# IoT_Shield_V1.net
KiCad netlist of a schematic drawn in EAGLE
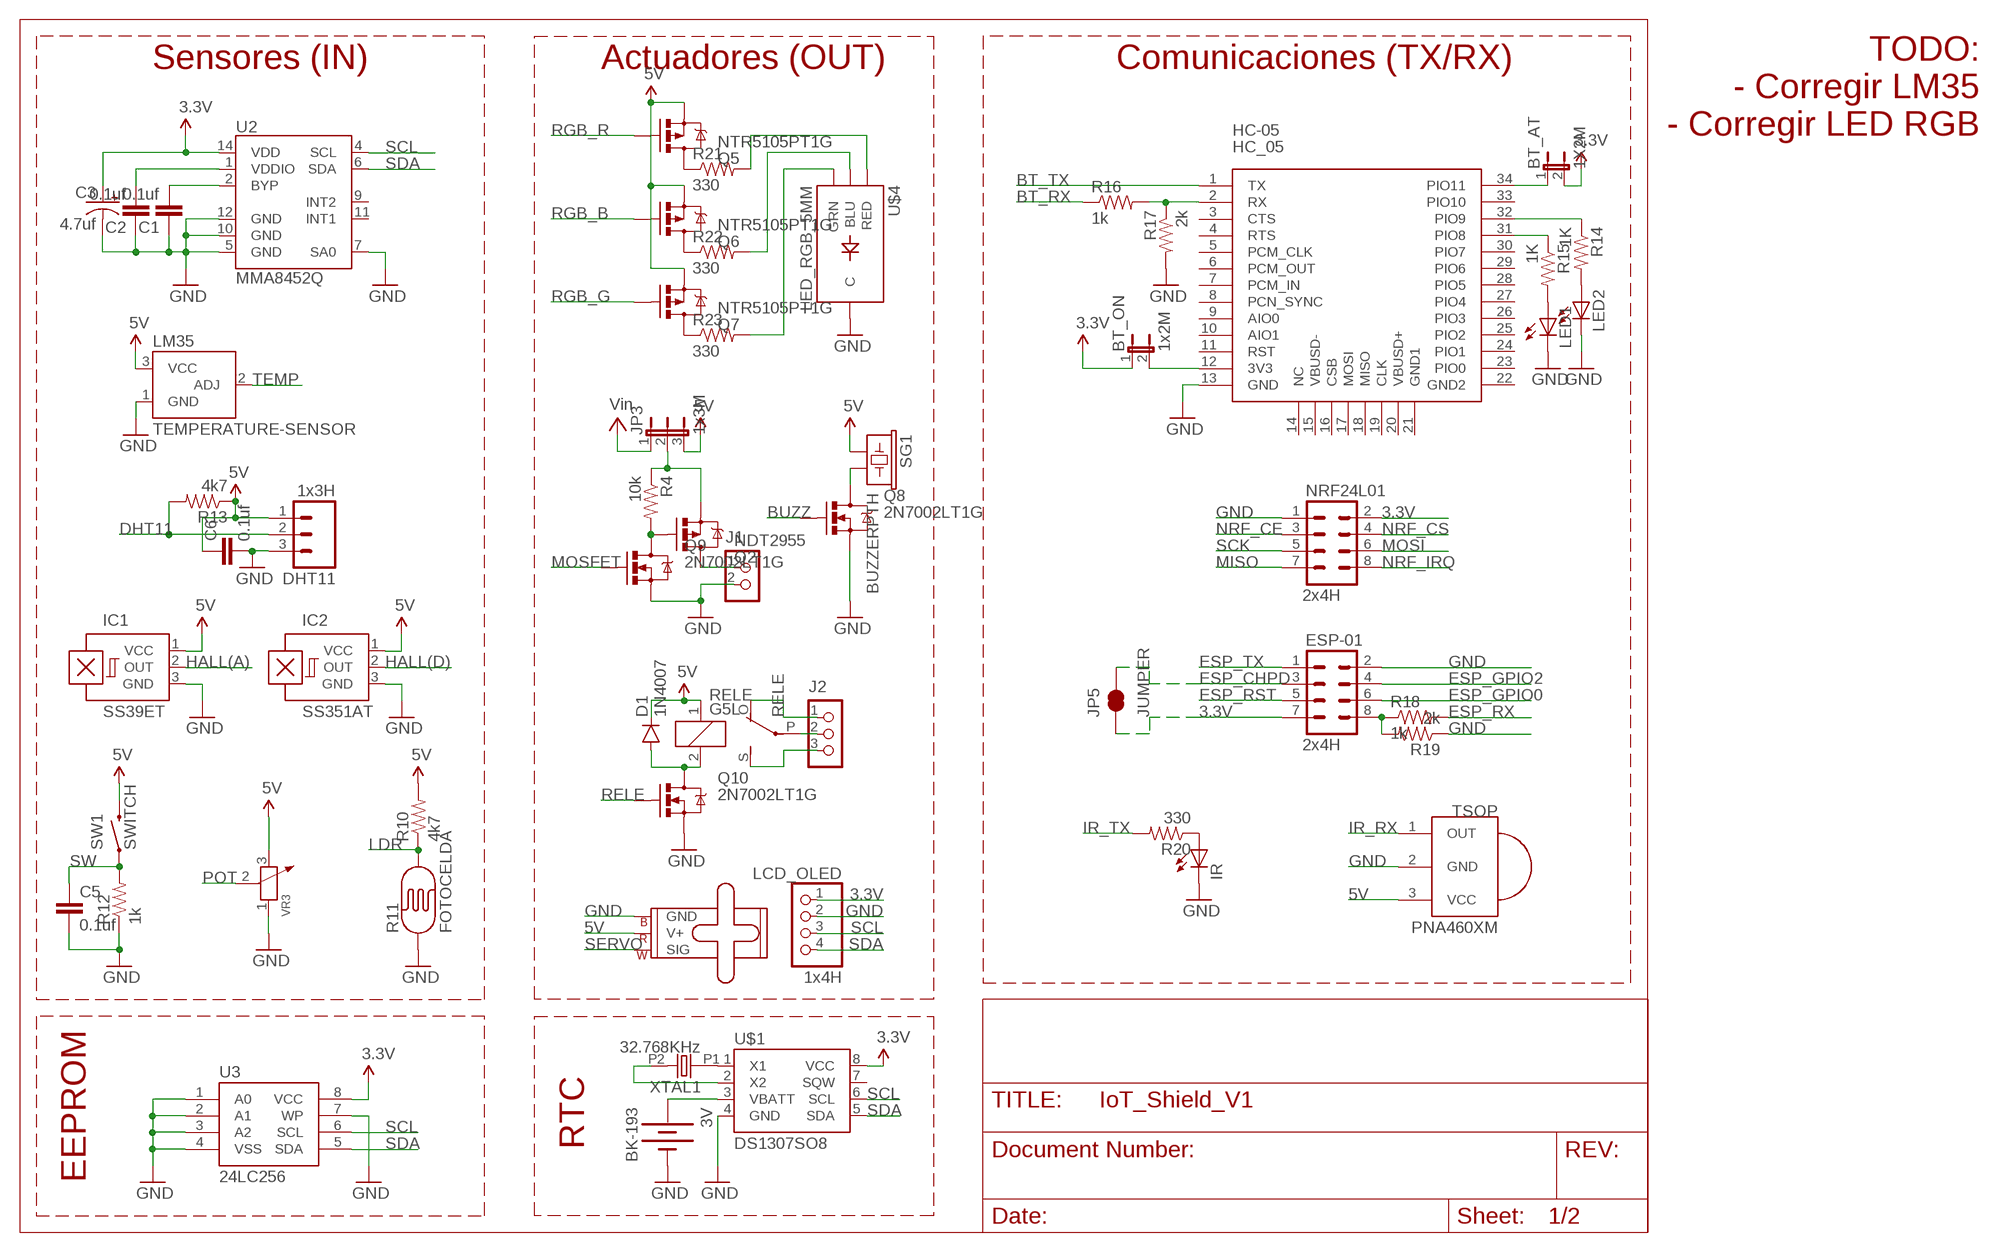
[diagram p0: schematic, sheet 1]
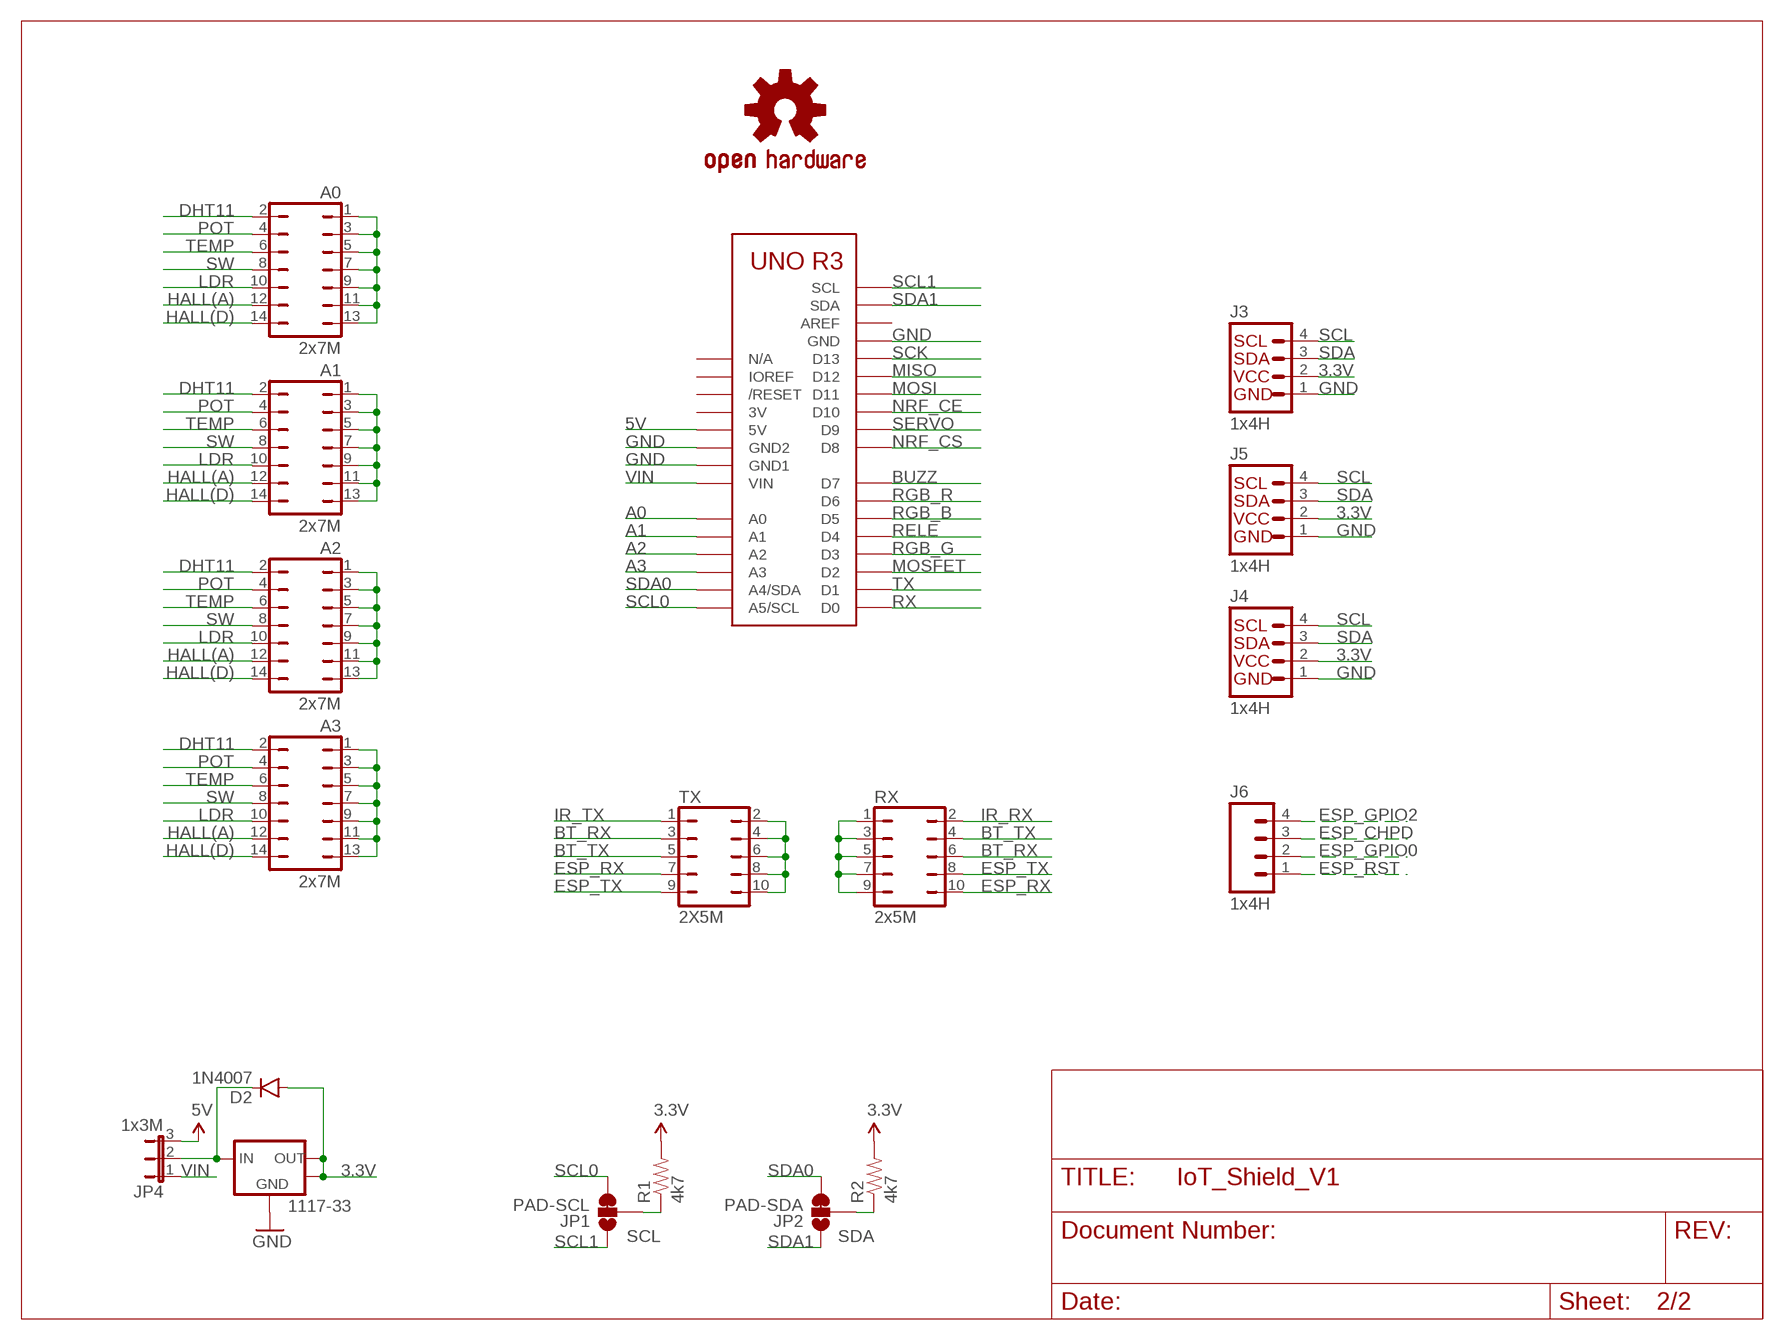
[diagram p1: schematic, sheet 2]

(export (version "E")
  (design (tool "Eeschema 10.0.6"))
  (components
    (comp (ref "3V")
      (value "BK-193")
      (footprint "eagle-import:BATTERY-20MMTH")
      (libsource (lib "eagle-import") (part "BK-193"))
    )
    (comp (ref "BT_AT")
      (value "1X2M")
      (footprint "eagle-import:JP1")
      (libsource (lib "eagle-import") (part "JP1E"))
    )
    (comp (ref "BT_ON")
      (value "1x2M")
      (footprint "eagle-import:JP1")
      (libsource (lib "eagle-import") (part "JP1E"))
    )
    (comp (ref "C1")
      (value "0.1uf")
      (footprint "eagle-import:0805")
      (libsource (lib "eagle-import") (part "CAP0805"))
    )
    (comp (ref "C2")
      (value "0.1uf")
      (footprint "eagle-import:0805")
      (libsource (lib "eagle-import") (part "CAP0805"))
    )
    (comp (ref "C3")
      (value "4.7uf")
      (footprint "eagle-import:EIA3528-KIT")
      (libsource (lib "eagle-import") (part "CAP_POL3528-KIT"))
    )
    (comp (ref "C5")
      (value "0.1uf")
      (footprint "eagle-import:0805")
      (libsource (lib "eagle-import") (part "SparkFun-Passives_CAP0805"))
    )
    (comp (ref "C6")
      (value "0.1uf")
      (footprint "eagle-import:0805")
      (libsource (lib "eagle-import") (part "SparkFun-Passives_CAP0805"))
    )
    (comp (ref "D1")
      (value "1N4007")
      (footprint "eagle-import:SMA-DIODE")
      (libsource (lib "eagle-import") (part "DIODESMA"))
    )
    (comp (ref "DHT11")
      (value "1x3H")
      (footprint "eagle-import:1X03_LOCK")
      (libsource (lib "eagle-import") (part "M03LOCK"))
    )
    (comp (ref "ESP-01")
      (value "2x4H")
      (footprint "eagle-import:2X4")
      (libsource (lib "eagle-import") (part "M04X2"))
    )
    (comp (ref "HC-05")
      (value "HC_05")
      (footprint "eagle-import:BLUETOOTH_SMD")
      (libsource (lib "eagle-import") (part "HC_05"))
    )
    (comp (ref "IC1")
      (value "SS39ET")
      (footprint "eagle-import:SOT23-W")
      (libsource (lib "eagle-import") (part "A12?LH02"))
    )
    (comp (ref "IC2")
      (value "SS351AT")
      (footprint "eagle-import:SOT23-W")
      (libsource (lib "eagle-import") (part "A12?LH02"))
    )
    (comp (ref "IR")
      (value "LEDIRL80A")
      (footprint "eagle-import:IRL80A")
      (libsource (lib "eagle-import") (part "led_LEDIRL80A"))
    )
    (comp (ref "J1")
      (value "CON_TERMINAL_BLOCK_02-5MM")
      (footprint "eagle-import:TERMINAL_BLOCK_2P_5")
      (libsource (lib "eagle-import") (part "CON_TERMINAL_BLOCK_02-5MM"))
    )
    (comp (ref "J2")
      (value "CON_TERMINAL_BLOCK_03-5MM")
      (footprint "eagle-import:TERMINAL_BLOCK_3P_5")
      (libsource (lib "eagle-import") (part "CON_TERMINAL_BLOCK_03-5MM"))
    )
    (comp (ref "JP3")
      (value "1x3M")
      (footprint "eagle-import:JP2")
      (libsource (lib "eagle-import") (part "JP2E"))
    )
    (comp (ref "JP5")
      (value "JUMPER")
      (footprint "eagle-import:PAD-JUMPER-2-NC_BY_TRACE_NO_SILK")
      (libsource (lib "eagle-import") (part "JUMPER-PAD-2-NC_BY_TRACENO_SILK"))
    )
    (comp (ref "LCD_OLED")
      (value "1x4H")
      (footprint "eagle-import:1X04")
      (libsource (lib "eagle-import") (part "PINHD-1X4"))
    )
    (comp (ref "LED1")
      (value "LEDCHIPLED_0805")
      (footprint "eagle-import:CHIPLED_0805")
      (libsource (lib "eagle-import") (part "LEDCHIPLED_0805"))
    )
    (comp (ref "LED2")
      (value "LEDCHIPLED_0805")
      (footprint "eagle-import:CHIPLED_0805")
      (libsource (lib "eagle-import") (part "LEDCHIPLED_0805"))
    )
    (comp (ref "LM35")
      (value "TEMPERATURE-SENSOR")
      (footprint "eagle-import:TO-92")
      (libsource (lib "eagle-import") (part "TEMPERATURE-SENSOR"))
    )
    (comp (ref "NRF24L01")
      (value "2x4H")
      (footprint "eagle-import:2X4")
      (libsource (lib "eagle-import") (part "M04X2"))
    )
    (comp (ref "Q2")
      (value "NDT2955")
      (footprint "eagle-import:SOT223")
      (libsource (lib "eagle-import") (part "NDT2955"))
    )
    (comp (ref "Q5")
      (value "NTR5105PT1G")
      (footprint "eagle-import:SOT23-3")
      (libsource (lib "eagle-import") (part "MOSFET-PCHANNEL"))
    )
    (comp (ref "Q6")
      (value "NTR5105PT1G")
      (footprint "eagle-import:SOT23-3")
      (libsource (lib "eagle-import") (part "MOSFET-PCHANNEL"))
    )
    (comp (ref "Q7")
      (value "NTR5105PT1G")
      (footprint "eagle-import:SOT23-3")
      (libsource (lib "eagle-import") (part "MOSFET-PCHANNEL"))
    )
    (comp (ref "Q8")
      (value "2N7002LT1G")
      (footprint "eagle-import:SOT23-3")
      (libsource (lib "eagle-import") (part "MOSFET-NCHANNELAO3404A"))
    )
    (comp (ref "Q9")
      (value "2N7002LT1G")
      (footprint "eagle-import:SOT23-3")
      (libsource (lib "eagle-import") (part "MOSFET-NCHANNELAO3404A"))
    )
    (comp (ref "Q10")
      (value "2N7002LT1G")
      (footprint "eagle-import:SOT23-3")
      (libsource (lib "eagle-import") (part "MOSFET-NCHANNELAO3404A"))
    )
    (comp (ref "R4")
      (value "10k")
      (footprint "eagle-import:0805")
      (libsource (lib "eagle-import") (part "RESISTOR0805-RES"))
    )
    (comp (ref "R10")
      (value "4k7")
      (footprint "eagle-import:0805")
      (libsource (lib "eagle-import") (part "RESISTOR0805-RES"))
    )
    (comp (ref "R11")
      (value "FOTOCELDA")
      (footprint "eagle-import:PHOTOCELL")
      (libsource (lib "eagle-import") (part "PHOTOCELLPTH"))
    )
    (comp (ref "R12")
      (value "1k")
      (footprint "eagle-import:0805")
      (libsource (lib "eagle-import") (part "RESISTOR0805-RES"))
    )
    (comp (ref "R13")
      (value "4k7")
      (footprint "eagle-import:0805")
      (libsource (lib "eagle-import") (part "RESISTOR0805-RES"))
    )
    (comp (ref "R14")
      (value "1K")
      (footprint "eagle-import:0805")
      (libsource (lib "eagle-import") (part "SparkFun-Resistors_RESISTOR0805-RES"))
    )
    (comp (ref "R15")
      (value "1K")
      (footprint "eagle-import:0805")
      (libsource (lib "eagle-import") (part "SparkFun-Resistors_RESISTOR0805-RES"))
    )
    (comp (ref "R16")
      (value "1k")
      (footprint "eagle-import:0805")
      (libsource (lib "eagle-import") (part "SparkFun-Resistors_RESISTOR0805-RES"))
    )
    (comp (ref "R17")
      (value "2k")
      (footprint "eagle-import:0805")
      (libsource (lib "eagle-import") (part "SparkFun-Resistors_RESISTOR0805-RES"))
    )
    (comp (ref "R18")
      (value "1k")
      (footprint "eagle-import:0805")
      (libsource (lib "eagle-import") (part "SparkFun-Resistors_RESISTOR0805-RES"))
    )
    (comp (ref "R19")
      (value "2k")
      (footprint "eagle-import:0805")
      (libsource (lib "eagle-import") (part "SparkFun-Resistors_RESISTOR0805-RES"))
    )
    (comp (ref "R20")
      (value "330")
      (footprint "eagle-import:1206")
      (libsource (lib "eagle-import") (part "RESISTOR1206"))
    )
    (comp (ref "R21")
      (value "330")
      (footprint "eagle-import:1206")
      (libsource (lib "eagle-import") (part "RESISTOR1206"))
    )
    (comp (ref "R22")
      (value "330")
      (footprint "eagle-import:1206")
      (libsource (lib "eagle-import") (part "RESISTOR1206"))
    )
    (comp (ref "R23")
      (value "330")
      (footprint "eagle-import:1206")
      (libsource (lib "eagle-import") (part "RESISTOR1206"))
    )
    (comp (ref "RELE")
      (value "G5L")
      (footprint "eagle-import:G5LE")
      (libsource (lib "eagle-import") (part "G5L"))
    )
    (comp (ref "SERVO")
      (value "1X3M")
      (footprint "eagle-import:1X03")
      (libsource (lib "eagle-import") (part "SMALL_SERVO"))
    )
    (comp (ref "SG1")
      (value "BUZZERPTH")
      (footprint "eagle-import:BUZZER-12MM")
      (libsource (lib "eagle-import") (part "BUZZERPTH"))
    )
    (comp (ref "SW1")
      (value "SWITCH")
      (footprint "eagle-import:TACTILE-PTH")
      (libsource (lib "eagle-import") (part "SWITCH-MOMENTARY-2PTH"))
    )
    (comp (ref "TSOP")
      (value "PNA460XM")
      (footprint "eagle-import:PNA460XM")
      (libsource (lib "eagle-import") (part "PNA460XM"))
    )
    (comp (ref "U$1")
      (value "DS1307SO8")
      (footprint "eagle-import:SO08")
      (libsource (lib "eagle-import") (part "DS1307SO8"))
    )
    (comp (ref "U$4")
      (value "LED_RGB_5MM")
      (footprint "eagle-import:LED_PIRANHA_5MM")
      (libsource (lib "eagle-import") (part "LED_PIRANHA_5MM"))
    )
    (comp (ref "U2")
      (value "MMA8452Q")
      (footprint "eagle-import:QFN-16_0.5MM")
      (libsource (lib "eagle-import") (part "MMA8452Q"))
    )
    (comp (ref "U3")
      (value "24LC256")
      (footprint "eagle-import:SO08")
      (libsource (lib "eagle-import") (part "EEPROM-I2CSMD"))
    )
    (comp (ref "VR3")
      (value "RES-ADJ'WH121-1'")
      (footprint "eagle-import:ADJR2+3P-16.0X12.0X18.0MM")
      (libsource (lib "eagle-import") (part "RES-ADJ'WH121-1'"))
    )
    (comp (ref "XTAL1")
      (value "32.768KHz")
      (footprint "eagle-import:TC-26")
      (libsource (lib "eagle-import") (part "OSC-XTALTC-26"))
    )
    (comp (ref "1117-33")
      (value "LV1117-33TO252")
      (footprint "eagle-import:TO252")
      (libsource (lib "eagle-import") (part "LV1117-33TO252"))
    )
    (comp (ref "A0")
      (value "2x7M")
      (footprint "eagle-import:JP7Q")
      (libsource (lib "eagle-import") (part "JP7Q"))
    )
    (comp (ref "A1")
      (value "2x7M")
      (footprint "eagle-import:JP7Q")
      (libsource (lib "eagle-import") (part "JP7Q"))
    )
    (comp (ref "A2")
      (value "2x7M")
      (footprint "eagle-import:JP7Q")
      (libsource (lib "eagle-import") (part "JP7Q"))
    )
    (comp (ref "A3")
      (value "2x7M")
      (footprint "eagle-import:JP7Q")
      (libsource (lib "eagle-import") (part "JP7Q"))
    )
    (comp (ref "D2")
      (value "1N4007")
      (footprint "eagle-import:SMA-DIODE")
      (libsource (lib "eagle-import") (part "DIODESMA"))
    )
    (comp (ref "J3")
      (value "1x4H")
      (footprint "eagle-import:1X04")
      (libsource (lib "eagle-import") (part "I2C_STANDARD"))
    )
    (comp (ref "J4")
      (value "1x4H")
      (footprint "eagle-import:1X04")
      (libsource (lib "eagle-import") (part "I2C_STANDARD"))
    )
    (comp (ref "J5")
      (value "1x4H")
      (footprint "eagle-import:1X04")
      (libsource (lib "eagle-import") (part "I2C_STANDARD"))
    )
    (comp (ref "J6")
      (value "1x4H")
      (footprint "eagle-import:1X04_LOCK")
      (libsource (lib "eagle-import") (part "M04LOCK"))
    )
    (comp (ref "JP1")
      (value "PAD-SCL")
      (footprint "eagle-import:PAD-JUMPER-3-2OF3_NC_BY_TRACE_YES_SILK_LARGE")
      (libsource (lib "eagle-import") (part "JUMPER-PAD-3-2OF3_NC_BY_TRACE_LARGE"))
    )
    (comp (ref "JP2")
      (value "PAD-SDA")
      (footprint "eagle-import:PAD-JUMPER-3-2OF3_NC_BY_TRACE_YES_SILK_LARGE")
      (libsource (lib "eagle-import") (part "JUMPER-PAD-3-2OF3_NC_BY_TRACE_LARGE"))
    )
    (comp (ref "JP4")
      (value "1x3M")
      (footprint "eagle-import:JP2")
      (libsource (lib "eagle-import") (part "JP2E"))
    )
    (comp (ref "LOGO1")
      (value "OSHW-LOGOL-COPPER")
      (footprint "eagle-import:OSHW-LOGO-L_COPPER")
      (libsource (lib "eagle-import") (part "OSHW-LOGOL-COPPER"))
    )
    (comp (ref "R1")
      (value "4k7")
      (footprint "eagle-import:0805")
      (libsource (lib "eagle-import") (part "RESISTOR0805-RES"))
    )
    (comp (ref "R2")
      (value "4k7")
      (footprint "eagle-import:0805")
      (libsource (lib "eagle-import") (part "RESISTOR0805-RES"))
    )
    (comp (ref "RX")
      (value "2x5M")
      (footprint "eagle-import:JP5Q")
      (libsource (lib "eagle-import") (part "JP5Q"))
    )
    (comp (ref "TX")
      (value "2X5M")
      (footprint "eagle-import:JP5Q")
      (libsource (lib "eagle-import") (part "JP5Q"))
    )
    (comp (ref "U1")
      (value "ARDUINOR3-DIMENSION")
      (footprint "eagle-import:ARDUINOR3")
      (libsource (lib "eagle-import") (part "ARDUINOR3-DIMENSION"))
    )
  )
  (nets
    (net (code "1") (name "3.3V") (class "Default")
      (node (ref "1117-33") (pin "2") (pinfunction "OUT_2") (pintype "output"))
      (node (ref "1117-33") (pin "4") (pinfunction "OUT_4") (pintype "output"))
      (node (ref "BT_AT") (pin "2") (pinfunction "2_2") (pintype "passive"))
      (node (ref "BT_ON") (pin "1") (pinfunction "1_1") (pintype "passive"))
      (node (ref "C3") (pin "A") (pinfunction "+_A") (pintype "passive"))
      (node (ref "D2") (pin "A") (pinfunction "A_A") (pintype "passive"))
      (node (ref "ESP-01") (pin "7") (pinfunction "7_7") (pintype "passive"))
      (node (ref "J3") (pin "2") (pinfunction "2_2") (pintype "passive"))
      (node (ref "J4") (pin "2") (pinfunction "2_2") (pintype "passive"))
      (node (ref "J5") (pin "2") (pinfunction "2_2") (pintype "passive"))
      (node (ref "JP5") (pin "1") (pinfunction "1_1") (pintype "passive"))
      (node (ref "LCD_OLED") (pin "1") (pinfunction "1_1") (pintype "passive"))
      (node (ref "NRF24L01") (pin "2") (pinfunction "2_2") (pintype "passive"))
      (node (ref "R1") (pin "2") (pinfunction "2_2") (pintype "passive"))
      (node (ref "R2") (pin "2") (pinfunction "2_2") (pintype "passive"))
      (node (ref "U$1") (pin "8") (pinfunction "VCC_8") (pintype "bidirectional"))
      (node (ref "U2") (pin "14") (pinfunction "VDD_14") (pintype "bidirectional"))
      (node (ref "U3") (pin "8") (pinfunction "VCC_8") (pintype "power_in"))
    )
    (net (code "2") (name "3V") (class "Default")
      (node (ref "U1") (pin "3V") (pinfunction "3V_3V") (pintype "power_in"))
    )
    (net (code "3") (name "5V") (class "Default")
      (node (ref "C6") (pin "1") (pinfunction "1_1") (pintype "passive"))
      (node (ref "D1") (pin "C") (pinfunction "C_C") (pintype "passive"))
      (node (ref "DHT11") (pin "1") (pinfunction "1_1") (pintype "passive"))
      (node (ref "IC1") (pin "1") (pinfunction "VCC_1") (pintype "power_in"))
      (node (ref "IC2") (pin "1") (pinfunction "VCC_1") (pintype "power_in"))
      (node (ref "JP3") (pin "3") (pinfunction "3_3") (pintype "passive"))
      (node (ref "JP4") (pin "3") (pinfunction "3_3") (pintype "passive"))
      (node (ref "LM35") (pin "3") (pinfunction "VCC_3") (pintype "bidirectional"))
      (node (ref "Q5") (pin "2") (pinfunction "S_2") (pintype "passive"))
      (node (ref "Q6") (pin "2") (pinfunction "S_2") (pintype "passive"))
      (node (ref "Q7") (pin "2") (pinfunction "S_2") (pintype "passive"))
      (node (ref "R10") (pin "2") (pinfunction "2_2") (pintype "passive"))
      (node (ref "R13") (pin "1") (pinfunction "1_1") (pintype "passive"))
      (node (ref "RELE") (pin "1") (pinfunction "1_1") (pintype "passive"))
      (node (ref "SERVO") (pin "2") (pinfunction "V+_2") (pintype "bidirectional"))
      (node (ref "SG1") (pin "+") (pinfunction "1_+") (pintype "passive"))
      (node (ref "SW1") (pin "3") (pinfunction "2_3") (pintype "passive"))
      (node (ref "TSOP") (pin "3") (pinfunction "VCC_3") (pintype "power_in"))
      (node (ref "U1") (pin "5V") (pinfunction "5V_5V") (pintype "power_in"))
      (node (ref "VR3") (pin "3") (pinfunction "3_3") (pintype "passive"))
    )
    (net (code "4") (name "A0") (class "Default")
      (node (ref "A0") (pin "1") (pinfunction "1_1") (pintype "passive"))
      (node (ref "A0") (pin "11") (pinfunction "11_11") (pintype "passive"))
      (node (ref "A0") (pin "13") (pinfunction "13_13") (pintype "passive"))
      (node (ref "A0") (pin "3") (pinfunction "3_3") (pintype "passive"))
      (node (ref "A0") (pin "5") (pinfunction "5_5") (pintype "passive"))
      (node (ref "A0") (pin "7") (pinfunction "7_7") (pintype "passive"))
      (node (ref "A0") (pin "9") (pinfunction "9_9") (pintype "passive"))
      (node (ref "U1") (pin "A0") (pinfunction "A0_A0") (pintype "bidirectional"))
    )
    (net (code "5") (name "A1") (class "Default")
      (node (ref "A1") (pin "1") (pinfunction "1_1") (pintype "passive"))
      (node (ref "A1") (pin "11") (pinfunction "11_11") (pintype "passive"))
      (node (ref "A1") (pin "13") (pinfunction "13_13") (pintype "passive"))
      (node (ref "A1") (pin "3") (pinfunction "3_3") (pintype "passive"))
      (node (ref "A1") (pin "5") (pinfunction "5_5") (pintype "passive"))
      (node (ref "A1") (pin "7") (pinfunction "7_7") (pintype "passive"))
      (node (ref "A1") (pin "9") (pinfunction "9_9") (pintype "passive"))
      (node (ref "U1") (pin "A1") (pinfunction "A1_A1") (pintype "bidirectional"))
    )
    (net (code "6") (name "A2") (class "Default")
      (node (ref "A2") (pin "1") (pinfunction "1_1") (pintype "passive"))
      (node (ref "A2") (pin "11") (pinfunction "11_11") (pintype "passive"))
      (node (ref "A2") (pin "13") (pinfunction "13_13") (pintype "passive"))
      (node (ref "A2") (pin "3") (pinfunction "3_3") (pintype "passive"))
      (node (ref "A2") (pin "5") (pinfunction "5_5") (pintype "passive"))
      (node (ref "A2") (pin "7") (pinfunction "7_7") (pintype "passive"))
      (node (ref "A2") (pin "9") (pinfunction "9_9") (pintype "passive"))
      (node (ref "U1") (pin "A2") (pinfunction "A2_A2") (pintype "bidirectional"))
    )
    (net (code "7") (name "A3") (class "Default")
      (node (ref "A3") (pin "1") (pinfunction "1_1") (pintype "passive"))
      (node (ref "A3") (pin "11") (pinfunction "11_11") (pintype "passive"))
      (node (ref "A3") (pin "13") (pinfunction "13_13") (pintype "passive"))
      (node (ref "A3") (pin "3") (pinfunction "3_3") (pintype "passive"))
      (node (ref "A3") (pin "5") (pinfunction "5_5") (pintype "passive"))
      (node (ref "A3") (pin "7") (pinfunction "7_7") (pintype "passive"))
      (node (ref "A3") (pin "9") (pinfunction "9_9") (pintype "passive"))
      (node (ref "U1") (pin "A3") (pinfunction "A3_A3") (pintype "bidirectional"))
    )
    (net (code "8") (name "BT_RX") (class "Default")
      (node (ref "R16") (pin "1") (pinfunction "1_1") (pintype "passive"))
      (node (ref "RX") (pin "6") (pinfunction "6_6") (pintype "passive"))
      (node (ref "TX") (pin "3") (pinfunction "3_3") (pintype "passive"))
    )
    (net (code "9") (name "BT_TX") (class "Default")
      (node (ref "HC-05") (pin "1") (pinfunction "TX_1") (pintype "bidirectional"))
      (node (ref "RX") (pin "4") (pinfunction "4_4") (pintype "passive"))
      (node (ref "TX") (pin "5") (pinfunction "5_5") (pintype "passive"))
    )
    (net (code "10") (name "BUZZ") (class "Default")
      (node (ref "Q8") (pin "1") (pinfunction "G_1") (pintype "passive"))
      (node (ref "U1") (pin "D7") (pinfunction "D7_D7") (pintype "bidirectional"))
    )
    (net (code "11") (name "DHT11") (class "Default")
      (node (ref "A0") (pin "2") (pinfunction "2_2") (pintype "passive"))
      (node (ref "A1") (pin "2") (pinfunction "2_2") (pintype "passive"))
      (node (ref "A2") (pin "2") (pinfunction "2_2") (pintype "passive"))
      (node (ref "A3") (pin "2") (pinfunction "2_2") (pintype "passive"))
      (node (ref "DHT11") (pin "2") (pinfunction "2_2") (pintype "passive"))
      (node (ref "R13") (pin "2") (pinfunction "2_2") (pintype "passive"))
    )
    (net (code "12") (name "ESP_CHPD") (class "Default")
      (node (ref "ESP-01") (pin "3") (pinfunction "3_3") (pintype "passive"))
      (node (ref "J6") (pin "3") (pinfunction "3_3") (pintype "passive"))
      (node (ref "JP5") (pin "2") (pinfunction "2_2") (pintype "passive"))
    )
    (net (code "13") (name "ESP_GPIO0") (class "Default")
      (node (ref "ESP-01") (pin "6") (pinfunction "6_6") (pintype "passive"))
      (node (ref "J6") (pin "2") (pinfunction "2_2") (pintype "passive"))
    )
    (net (code "14") (name "ESP_GPIO2") (class "Default")
      (node (ref "ESP-01") (pin "4") (pinfunction "4_4") (pintype "passive"))
      (node (ref "J6") (pin "4") (pinfunction "4_4") (pintype "passive"))
    )
    (net (code "15") (name "ESP_RST") (class "Default")
      (node (ref "ESP-01") (pin "5") (pinfunction "5_5") (pintype "passive"))
      (node (ref "J6") (pin "1") (pinfunction "1_1") (pintype "passive"))
    )
    (net (code "16") (name "ESP_RX") (class "Default")
      (node (ref "R18") (pin "2") (pinfunction "2_2") (pintype "passive"))
      (node (ref "RX") (pin "10") (pinfunction "10_10") (pintype "passive"))
      (node (ref "TX") (pin "7") (pinfunction "7_7") (pintype "passive"))
    )
    (net (code "17") (name "ESP_TX") (class "Default")
      (node (ref "ESP-01") (pin "1") (pinfunction "1_1") (pintype "passive"))
      (node (ref "RX") (pin "8") (pinfunction "8_8") (pintype "passive"))
      (node (ref "TX") (pin "9") (pinfunction "9_9") (pintype "passive"))
    )
    (net (code "18") (name "GND") (class "Default")
      (node (ref "1117-33") (pin "1") (pinfunction "ADJ_1") (pintype "input"))
      (node (ref "3V") (pin "P1-") (pinfunction "-_P1-") (pintype "power_in"))
      (node (ref "C1") (pin "1") (pinfunction "1_1") (pintype "passive"))
      (node (ref "C2") (pin "1") (pinfunction "1_1") (pintype "passive"))
      (node (ref "C3") (pin "C") (pinfunction "-_C") (pintype "passive"))
      (node (ref "C5") (pin "2") (pinfunction "2_2") (pintype "passive"))
      (node (ref "C6") (pin "2") (pinfunction "2_2") (pintype "passive"))
      (node (ref "DHT11") (pin "3") (pinfunction "3_3") (pintype "passive"))
      (node (ref "ESP-01") (pin "2") (pinfunction "2_2") (pintype "passive"))
      (node (ref "HC-05") (pin "13") (pinfunction "GND_13") (pintype "bidirectional"))
      (node (ref "IC1") (pin "3") (pinfunction "GND_3") (pintype "power_in"))
      (node (ref "IC2") (pin "3") (pinfunction "GND_3") (pintype "power_in"))
      (node (ref "IR") (pin "K") (pinfunction "C_K") (pintype "passive"))
      (node (ref "J1") (pin "2") (pinfunction "2_2") (pintype "passive"))
      (node (ref "J3") (pin "1") (pinfunction "1_1") (pintype "passive"))
      (node (ref "J4") (pin "1") (pinfunction "1_1") (pintype "passive"))
      (node (ref "J5") (pin "1") (pinfunction "1_1") (pintype "passive"))
      (node (ref "LCD_OLED") (pin "2") (pinfunction "2_2") (pintype "passive"))
      (node (ref "LED1") (pin "C") (pinfunction "C_C") (pintype "passive"))
      (node (ref "LED2") (pin "C") (pinfunction "C_C") (pintype "passive"))
      (node (ref "LM35") (pin "1") (pinfunction "GND_1") (pintype "bidirectional"))
      (node (ref "NRF24L01") (pin "1") (pinfunction "1_1") (pintype "passive"))
      (node (ref "Q10") (pin "2") (pinfunction "S_2") (pintype "passive"))
      (node (ref "Q8") (pin "2") (pinfunction "S_2") (pintype "passive"))
      (node (ref "Q9") (pin "2") (pinfunction "S_2") (pintype "passive"))
      (node (ref "R11") (pin "1") (pinfunction "P$1_1") (pintype "bidirectional"))
      (node (ref "R12") (pin "1") (pinfunction "1_1") (pintype "passive"))
      (node (ref "R17") (pin "2") (pinfunction "2_2") (pintype "passive"))
      (node (ref "R19") (pin "1") (pinfunction "1_1") (pintype "passive"))
      (node (ref "SERVO") (pin "3") (pinfunction "GND_3") (pintype "bidirectional"))
      (node (ref "TSOP") (pin "2") (pinfunction "GND_2") (pintype "power_in"))
      (node (ref "U$1") (pin "4") (pinfunction "GND_4") (pintype "bidirectional"))
      (node (ref "U$4") (pin "-") (pinfunction "C_-") (pintype "bidirectional"))
      (node (ref "U1") (pin "GND") (pinfunction "GND_GND") (pintype "power_in"))
      (node (ref "U1") (pin "GND1") (pinfunction "GND1_GND1") (pintype "power_in"))
      (node (ref "U1") (pin "GND2") (pinfunction "GND2_GND2") (pintype "power_in"))
      (node (ref "U2") (pin "10") (pinfunction "GND_10") (pintype "bidirectional"))
      (node (ref "U2") (pin "12") (pinfunction "GND_12") (pintype "bidirectional"))
      (node (ref "U2") (pin "5") (pinfunction "GND_5") (pintype "bidirectional"))
      (node (ref "U2") (pin "7") (pinfunction "SA0_7") (pintype "bidirectional"))
      (node (ref "U3") (pin "1") (pinfunction "A0_1") (pintype "bidirectional"))
      (node (ref "U3") (pin "2") (pinfunction "A1_2") (pintype "bidirectional"))
      (node (ref "U3") (pin "3") (pinfunction "A2_3") (pintype "bidirectional"))
      (node (ref "U3") (pin "4") (pinfunction "VSS_4") (pintype "power_in"))
      (node (ref "U3") (pin "7") (pinfunction "WP_7") (pintype "bidirectional"))
      (node (ref "VR3") (pin "1") (pinfunction "1_1") (pintype "passive"))
    )
    (net (code "19") (name "HALL(A)") (class "Default")
      (node (ref "A0") (pin "12") (pinfunction "12_12") (pintype "passive"))
      (node (ref "A1") (pin "12") (pinfunction "12_12") (pintype "passive"))
      (node (ref "A2") (pin "12") (pinfunction "12_12") (pintype "passive"))
      (node (ref "A3") (pin "12") (pinfunction "12_12") (pintype "passive"))
      (node (ref "IC1") (pin "2") (pinfunction "OUT_2") (pintype "output"))
    )
    (net (code "20") (name "HALL(D)") (class "Default")
      (node (ref "A0") (pin "14") (pinfunction "14_14") (pintype "passive"))
      (node (ref "A1") (pin "14") (pinfunction "14_14") (pintype "passive"))
      (node (ref "A2") (pin "14") (pinfunction "14_14") (pintype "passive"))
      (node (ref "A3") (pin "14") (pinfunction "14_14") (pintype "passive"))
      (node (ref "IC2") (pin "2") (pinfunction "OUT_2") (pintype "output"))
    )
    (net (code "21") (name "IR_RX") (class "Default")
      (node (ref "RX") (pin "2") (pinfunction "2_2") (pintype "passive"))
      (node (ref "TSOP") (pin "1") (pinfunction "OUT_1") (pintype "output"))
    )
    (net (code "22") (name "IR_TX") (class "Default")
      (node (ref "R20") (pin "2") (pinfunction "2_2") (pintype "passive"))
      (node (ref "TX") (pin "1") (pinfunction "1_1") (pintype "passive"))
    )
    (net (code "23") (name "LDR") (class "Default")
      (node (ref "A0") (pin "10") (pinfunction "10_10") (pintype "passive"))
      (node (ref "A1") (pin "10") (pinfunction "10_10") (pintype "passive"))
      (node (ref "A2") (pin "10") (pinfunction "10_10") (pintype "passive"))
      (node (ref "A3") (pin "10") (pinfunction "10_10") (pintype "passive"))
      (node (ref "R10") (pin "1") (pinfunction "1_1") (pintype "passive"))
      (node (ref "R11") (pin "2") (pinfunction "P$2_2") (pintype "bidirectional"))
    )
    (net (code "24") (name "MISO") (class "Default")
      (node (ref "NRF24L01") (pin "7") (pinfunction "7_7") (pintype "passive"))
      (node (ref "U1") (pin "D12") (pinfunction "D12_D12") (pintype "bidirectional"))
    )
    (net (code "25") (name "MOSFET") (class "Default")
      (node (ref "Q9") (pin "1") (pinfunction "G_1") (pintype "passive"))
      (node (ref "U1") (pin "D2") (pinfunction "D2_D2") (pintype "bidirectional"))
    )
    (net (code "26") (name "MOSI") (class "Default")
      (node (ref "NRF24L01") (pin "6") (pinfunction "6_6") (pintype "passive"))
      (node (ref "U1") (pin "D11") (pinfunction "D11_D11") (pintype "bidirectional"))
    )
    (net (code "27") (name "NRF_CE") (class "Default")
      (node (ref "NRF24L01") (pin "3") (pinfunction "3_3") (pintype "passive"))
      (node (ref "U1") (pin "D10") (pinfunction "D10_D10") (pintype "bidirectional"))
    )
    (net (code "28") (name "NRF_CS") (class "Default")
      (node (ref "NRF24L01") (pin "4") (pinfunction "4_4") (pintype "passive"))
      (node (ref "U1") (pin "D8") (pinfunction "D8_D8") (pintype "bidirectional"))
    )
    (net (code "29") (name "NRF_IRQ") (class "Default")
      (node (ref "NRF24L01") (pin "8") (pinfunction "8_8") (pintype "passive"))
    )
    (net (code "30") (name "Net-(1117-33-IN)") (class "Default")
      (node (ref "1117-33") (pin "3") (pinfunction "IN_3") (pintype "input"))
      (node (ref "D2") (pin "C") (pinfunction "C_C") (pintype "passive"))
      (node (ref "JP4") (pin "2") (pinfunction "2_2") (pintype "passive"))
    )
    (net (code "31") (name "Net-(ESP-01-Pad8)") (class "Default")
      (node (ref "ESP-01") (pin "8") (pinfunction "8_8") (pintype "passive"))
      (node (ref "R18") (pin "1") (pinfunction "1_1") (pintype "passive"))
      (node (ref "R19") (pin "2") (pinfunction "2_2") (pintype "passive"))
    )
    (net (code "32") (name "Net-(HC-05-3V3)") (class "Default")
      (node (ref "BT_ON") (pin "2") (pinfunction "2_2") (pintype "passive"))
      (node (ref "HC-05") (pin "12") (pinfunction "3V3_12") (pintype "bidirectional"))
    )
    (net (code "33") (name "Net-(HC-05-PIO8)") (class "Default")
      (node (ref "HC-05") (pin "31") (pinfunction "PIO8_31") (pintype "bidirectional"))
      (node (ref "R15") (pin "1") (pinfunction "1_1") (pintype "passive"))
    )
    (net (code "34") (name "Net-(HC-05-PIO9)") (class "Default")
      (node (ref "HC-05") (pin "32") (pinfunction "PIO9_32") (pintype "bidirectional"))
      (node (ref "R14") (pin "1") (pinfunction "1_1") (pintype "passive"))
    )
    (net (code "35") (name "Net-(HC-05-PIO11)") (class "Default")
      (node (ref "BT_AT") (pin "1") (pinfunction "1_1") (pintype "passive"))
      (node (ref "HC-05") (pin "34") (pinfunction "PIO11_34") (pintype "bidirectional"))
    )
    (net (code "36") (name "Net-(HC-05-RX)") (class "Default")
      (node (ref "HC-05") (pin "2") (pinfunction "RX_2") (pintype "bidirectional"))
      (node (ref "R16") (pin "2") (pinfunction "2_2") (pintype "passive"))
      (node (ref "R17") (pin "1") (pinfunction "1_1") (pintype "passive"))
    )
    (net (code "37") (name "Net-(IR-PadA)") (class "Default")
      (node (ref "IR") (pin "A") (pinfunction "A_A") (pintype "passive"))
      (node (ref "R20") (pin "1") (pinfunction "1_1") (pintype "passive"))
    )
    (net (code "38") (name "Net-(J1-Pad1)") (class "Default")
      (node (ref "J1") (pin "1") (pinfunction "1_1") (pintype "passive"))
      (node (ref "Q2") (pin "2") (pinfunction "D_2") (pintype "passive"))
      (node (ref "Q2") (pin "4") (pinfunction "D_4") (pintype "passive"))
    )
    (net (code "39") (name "Net-(J2-Pad1)") (class "Default")
      (node (ref "J2") (pin "1") (pinfunction "1_1") (pintype "bidirectional"))
      (node (ref "RELE") (pin "O") (pinfunction "O_O") (pintype "passive"))
    )
    (net (code "40") (name "Net-(J2-Pad2)") (class "Default")
      (node (ref "J2") (pin "2") (pinfunction "2_2") (pintype "bidirectional"))
      (node (ref "RELE") (pin "P") (pinfunction "P_P") (pintype "passive"))
    )
    (net (code "41") (name "Net-(J2-Pad3)") (class "Default")
      (node (ref "J2") (pin "3") (pinfunction "3_3") (pintype "bidirectional"))
      (node (ref "RELE") (pin "S") (pinfunction "S_S") (pintype "passive"))
    )
    (net (code "42") (name "Net-(LED1-PadA)") (class "Default")
      (node (ref "LED1") (pin "A") (pinfunction "A_A") (pintype "passive"))
      (node (ref "R15") (pin "2") (pinfunction "2_2") (pintype "passive"))
    )
    (net (code "43") (name "Net-(LED2-PadA)") (class "Default")
      (node (ref "LED2") (pin "A") (pinfunction "A_A") (pintype "passive"))
      (node (ref "R14") (pin "2") (pinfunction "2_2") (pintype "passive"))
    )
    (net (code "44") (name "Net-(Q2-G)") (class "Default")
      (node (ref "Q2") (pin "1") (pinfunction "G_1") (pintype "passive"))
      (node (ref "Q9") (pin "3") (pinfunction "D_3") (pintype "passive"))
      (node (ref "R4") (pin "2") (pinfunction "2_2") (pintype "passive"))
    )
    (net (code "45") (name "Net-(Q2-S)") (class "Default")
      (node (ref "JP3") (pin "2") (pinfunction "2_2") (pintype "passive"))
      (node (ref "Q2") (pin "3") (pinfunction "S_3") (pintype "passive"))
      (node (ref "R4") (pin "1") (pinfunction "1_1") (pintype "passive"))
    )
    (net (code "46") (name "Net-(Q5-D)") (class "Default")
      (node (ref "Q5") (pin "3") (pinfunction "D_3") (pintype "passive"))
      (node (ref "R21") (pin "1") (pinfunction "1_1") (pintype "passive"))
    )
    (net (code "47") (name "Net-(Q6-D)") (class "Default")
      (node (ref "Q6") (pin "3") (pinfunction "D_3") (pintype "passive"))
      (node (ref "R22") (pin "1") (pinfunction "1_1") (pintype "passive"))
    )
    (net (code "48") (name "Net-(Q7-D)") (class "Default")
      (node (ref "Q7") (pin "3") (pinfunction "D_3") (pintype "passive"))
      (node (ref "R23") (pin "1") (pinfunction "1_1") (pintype "passive"))
    )
    (net (code "49") (name "Net-(Q8-D)") (class "Default")
      (node (ref "Q8") (pin "3") (pinfunction "D_3") (pintype "passive"))
      (node (ref "SG1") (pin "-") (pinfunction "2_-") (pintype "passive"))
    )
    (net (code "50") (name "Net-(Q10-D)") (class "Default")
      (node (ref "D1") (pin "A") (pinfunction "A_A") (pintype "passive"))
      (node (ref "Q10") (pin "3") (pinfunction "D_3") (pintype "passive"))
      (node (ref "RELE") (pin "2") (pinfunction "2_2") (pintype "passive"))
    )
    (net (code "51") (name "Net-(U$1-VBATT)") (class "Default")
      (node (ref "3V") (pin "P2+") (pinfunction "+_P2+") (pintype "power_in"))
      (node (ref "3V") (pin "P3+") (pinfunction "+_P3+") (pintype "power_in"))
      (node (ref "U$1") (pin "3") (pinfunction "VBATT_3") (pintype "bidirectional"))
    )
    (net (code "52") (name "Net-(U$1-X1)") (class "Default")
      (node (ref "U$1") (pin "1") (pinfunction "X1_1") (pintype "bidirectional"))
      (node (ref "XTAL1") (pin "P1") (pinfunction "1_P1") (pintype "passive"))
    )
    (net (code "53") (name "Net-(U$1-X2)") (class "Default")
      (node (ref "U$1") (pin "2") (pinfunction "X2_2") (pintype "bidirectional"))
      (node (ref "XTAL1") (pin "P2") (pinfunction "2_P2") (pintype "passive"))
    )
    (net (code "54") (name "Net-(U$4-BLU)") (class "Default")
      (node (ref "R22") (pin "2") (pinfunction "2_2") (pintype "passive"))
      (node (ref "U$4") (pin "B") (pinfunction "BLU_B") (pintype "bidirectional"))
    )
    (net (code "55") (name "Net-(U$4-GRN)") (class "Default")
      (node (ref "R23") (pin "2") (pinfunction "2_2") (pintype "passive"))
      (node (ref "U$4") (pin "G") (pinfunction "GRN_G") (pintype "bidirectional"))
    )
    (net (code "56") (name "Net-(U$4-RED)") (class "Default")
      (node (ref "R21") (pin "2") (pinfunction "2_2") (pintype "passive"))
      (node (ref "U$4") (pin "R") (pinfunction "RED_R") (pintype "bidirectional"))
    )
    (net (code "57") (name "Net-(U2-BYP)") (class "Default")
      (node (ref "C1") (pin "2") (pinfunction "2_2") (pintype "passive"))
      (node (ref "U2") (pin "2") (pinfunction "BYP_2") (pintype "bidirectional"))
    )
    (net (code "58") (name "Net-(U2-VDDIO)") (class "Default")
      (node (ref "C2") (pin "2") (pinfunction "2_2") (pintype "passive"))
      (node (ref "U2") (pin "1") (pinfunction "VDDIO_1") (pintype "bidirectional"))
    )
    (net (code "59") (name "POT") (class "Default")
      (node (ref "A0") (pin "4") (pinfunction "4_4") (pintype "passive"))
      (node (ref "A1") (pin "4") (pinfunction "4_4") (pintype "passive"))
      (node (ref "A2") (pin "4") (pinfunction "4_4") (pintype "passive"))
      (node (ref "A3") (pin "4") (pinfunction "4_4") (pintype "passive"))
      (node (ref "VR3") (pin "2") (pinfunction "2_2") (pintype "passive"))
    )
    (net (code "60") (name "RELE") (class "Default")
      (node (ref "Q10") (pin "1") (pinfunction "G_1") (pintype "passive"))
      (node (ref "U1") (pin "D4") (pinfunction "D4_D4") (pintype "bidirectional"))
    )
    (net (code "61") (name "RGB_B") (class "Default")
      (node (ref "Q6") (pin "1") (pinfunction "G_1") (pintype "passive"))
      (node (ref "U1") (pin "D5") (pinfunction "D5_D5") (pintype "bidirectional"))
    )
    (net (code "62") (name "RGB_G") (class "Default")
      (node (ref "Q7") (pin "1") (pinfunction "G_1") (pintype "passive"))
      (node (ref "U1") (pin "D3") (pinfunction "D3_D3") (pintype "bidirectional"))
    )
    (net (code "63") (name "RGB_R") (class "Default")
      (node (ref "Q5") (pin "1") (pinfunction "G_1") (pintype "passive"))
      (node (ref "U1") (pin "D6") (pinfunction "D6_D6") (pintype "bidirectional"))
    )
    (net (code "64") (name "RX") (class "Default")
      (node (ref "RX") (pin "1") (pinfunction "1_1") (pintype "passive"))
      (node (ref "RX") (pin "3") (pinfunction "3_3") (pintype "passive"))
      (node (ref "RX") (pin "5") (pinfunction "5_5") (pintype "passive"))
      (node (ref "RX") (pin "7") (pinfunction "7_7") (pintype "passive"))
      (node (ref "RX") (pin "9") (pinfunction "9_9") (pintype "passive"))
      (node (ref "U1") (pin "D0") (pinfunction "D0_D0") (pintype "bidirectional"))
    )
    (net (code "65") (name "SCK") (class "Default")
      (node (ref "NRF24L01") (pin "5") (pinfunction "5_5") (pintype "passive"))
      (node (ref "U1") (pin "D13") (pinfunction "D13_D13") (pintype "bidirectional"))
    )
    (net (code "66") (name "SCL") (class "Default")
      (node (ref "J3") (pin "4") (pinfunction "4_4") (pintype "passive"))
      (node (ref "J4") (pin "4") (pinfunction "4_4") (pintype "passive"))
      (node (ref "J5") (pin "4") (pinfunction "4_4") (pintype "passive"))
      (node (ref "JP1") (pin "2") (pinfunction "2_2") (pintype "passive"))
      (node (ref "LCD_OLED") (pin "3") (pinfunction "3_3") (pintype "passive"))
      (node (ref "R1") (pin "1") (pinfunction "1_1") (pintype "passive"))
      (node (ref "U$1") (pin "6") (pinfunction "SCL_6") (pintype "bidirectional"))
      (node (ref "U2") (pin "4") (pinfunction "SCL_4") (pintype "bidirectional"))
      (node (ref "U3") (pin "6") (pinfunction "SCL_6") (pintype "bidirectional"))
    )
    (net (code "67") (name "SCL0") (class "Default")
      (node (ref "JP1") (pin "3") (pinfunction "3_3") (pintype "passive"))
      (node (ref "U1") (pin "A5") (pinfunction "A5/SCL_A5") (pintype "bidirectional"))
    )
    (net (code "68") (name "SCL1") (class "Default")
      (node (ref "JP1") (pin "1") (pinfunction "1_1") (pintype "passive"))
      (node (ref "U1") (pin "SCL") (pinfunction "SCL_SCL") (pintype "bidirectional"))
    )
    (net (code "69") (name "SDA") (class "Default")
      (node (ref "J3") (pin "3") (pinfunction "3_3") (pintype "passive"))
      (node (ref "J4") (pin "3") (pinfunction "3_3") (pintype "passive"))
      (node (ref "J5") (pin "3") (pinfunction "3_3") (pintype "passive"))
      (node (ref "JP2") (pin "2") (pinfunction "2_2") (pintype "passive"))
      (node (ref "LCD_OLED") (pin "4") (pinfunction "4_4") (pintype "passive"))
      (node (ref "R2") (pin "1") (pinfunction "1_1") (pintype "passive"))
      (node (ref "U$1") (pin "5") (pinfunction "SDA_5") (pintype "bidirectional"))
      (node (ref "U2") (pin "6") (pinfunction "SDA_6") (pintype "bidirectional"))
      (node (ref "U3") (pin "5") (pinfunction "SDA_5") (pintype "bidirectional"))
    )
    (net (code "70") (name "SDA0") (class "Default")
      (node (ref "JP2") (pin "3") (pinfunction "3_3") (pintype "passive"))
      (node (ref "U1") (pin "A4") (pinfunction "A4/SDA_A4") (pintype "bidirectional"))
    )
    (net (code "71") (name "SDA1") (class "Default")
      (node (ref "JP2") (pin "1") (pinfunction "1_1") (pintype "passive"))
      (node (ref "U1") (pin "SDA") (pinfunction "SDA_SDA") (pintype "bidirectional"))
    )
    (net (code "72") (name "SERVO") (class "Default")
      (node (ref "SERVO") (pin "1") (pinfunction "SIG_1") (pintype "bidirectional"))
      (node (ref "U1") (pin "D9") (pinfunction "D9_D9") (pintype "bidirectional"))
    )
    (net (code "73") (name "SW") (class "Default")
      (node (ref "A0") (pin "8") (pinfunction "8_8") (pintype "passive"))
      (node (ref "A1") (pin "8") (pinfunction "8_8") (pintype "passive"))
      (node (ref "A2") (pin "8") (pinfunction "8_8") (pintype "passive"))
      (node (ref "A3") (pin "8") (pinfunction "8_8") (pintype "passive"))
      (node (ref "C5") (pin "1") (pinfunction "1_1") (pintype "passive"))
      (node (ref "R12") (pin "2") (pinfunction "2_2") (pintype "passive"))
      (node (ref "SW1") (pin "1") (pinfunction "1_1") (pintype "passive"))
    )
    (net (code "74") (name "TEMP") (class "Default")
      (node (ref "A0") (pin "6") (pinfunction "6_6") (pintype "passive"))
      (node (ref "A1") (pin "6") (pinfunction "6_6") (pintype "passive"))
      (node (ref "A2") (pin "6") (pinfunction "6_6") (pintype "passive"))
      (node (ref "A3") (pin "6") (pinfunction "6_6") (pintype "passive"))
      (node (ref "LM35") (pin "2") (pinfunction "ADJ_2") (pintype "bidirectional"))
    )
    (net (code "75") (name "TX") (class "Default")
      (node (ref "TX") (pin "10") (pinfunction "10_10") (pintype "passive"))
      (node (ref "TX") (pin "2") (pinfunction "2_2") (pintype "passive"))
      (node (ref "TX") (pin "4") (pinfunction "4_4") (pintype "passive"))
      (node (ref "TX") (pin "6") (pinfunction "6_6") (pintype "passive"))
      (node (ref "TX") (pin "8") (pinfunction "8_8") (pintype "passive"))
      (node (ref "U1") (pin "D1") (pinfunction "D1_D1") (pintype "bidirectional"))
    )
    (net (code "76") (name "VIN") (class "Default")
      (node (ref "JP3") (pin "1") (pinfunction "1_1") (pintype "passive"))
      (node (ref "JP4") (pin "1") (pinfunction "1_1") (pintype "passive"))
      (node (ref "U1") (pin "VIN") (pinfunction "VIN_VIN") (pintype "power_in"))
    )
    (net (code "77") (name "unconnected-(HC-05-AIO0-Pad9)") (class "Default")
      (node (ref "HC-05") (pin "9") (pinfunction "AIO0_9") (pintype "bidirectional"))
    )
    (net (code "78") (name "unconnected-(HC-05-AIO1-Pad10)") (class "Default")
      (node (ref "HC-05") (pin "10") (pinfunction "AIO1_10") (pintype "bidirectional"))
    )
    (net (code "79") (name "unconnected-(HC-05-CLK-Pad19)") (class "Default")
      (node (ref "HC-05") (pin "19") (pinfunction "CLK_19") (pintype "bidirectional"))
    )
    (net (code "80") (name "unconnected-(HC-05-CSB-Pad16)") (class "Default")
      (node (ref "HC-05") (pin "16") (pinfunction "CSB_16") (pintype "bidirectional"))
    )
    (net (code "81") (name "unconnected-(HC-05-CTS-Pad3)") (class "Default")
      (node (ref "HC-05") (pin "3") (pinfunction "CTS_3") (pintype "bidirectional"))
    )
    (net (code "82") (name "unconnected-(HC-05-GND1-Pad21)") (class "Default")
      (node (ref "HC-05") (pin "21") (pinfunction "GND1_21") (pintype "bidirectional"))
    )
    (net (code "83") (name "unconnected-(HC-05-GND2-Pad22)") (class "Default")
      (node (ref "HC-05") (pin "22") (pinfunction "GND2_22") (pintype "bidirectional"))
    )
    (net (code "84") (name "unconnected-(HC-05-MISO-Pad18)") (class "Default")
      (node (ref "HC-05") (pin "18") (pinfunction "MISO_18") (pintype "bidirectional"))
    )
    (net (code "85") (name "unconnected-(HC-05-MOSI-Pad17)") (class "Default")
      (node (ref "HC-05") (pin "17") (pinfunction "MOSI_17") (pintype "bidirectional"))
    )
    (net (code "86") (name "unconnected-(HC-05-NC-Pad14)") (class "Default")
      (node (ref "HC-05") (pin "14") (pinfunction "NC_14") (pintype "bidirectional"))
    )
    (net (code "87") (name "unconnected-(HC-05-PCM_CLK-Pad5)") (class "Default")
      (node (ref "HC-05") (pin "5") (pinfunction "PCM_CLK_5") (pintype "bidirectional"))
    )
    (net (code "88") (name "unconnected-(HC-05-PCM_IN-Pad7)") (class "Default")
      (node (ref "HC-05") (pin "7") (pinfunction "PCM_IN_7") (pintype "bidirectional"))
    )
    (net (code "89") (name "unconnected-(HC-05-PCM_OUT-Pad6)") (class "Default")
      (node (ref "HC-05") (pin "6") (pinfunction "PCM_OUT_6") (pintype "bidirectional"))
    )
    (net (code "90") (name "unconnected-(HC-05-PCN_SYNC-Pad8)") (class "Default")
      (node (ref "HC-05") (pin "8") (pinfunction "PCN_SYNC_8") (pintype "bidirectional"))
    )
    (net (code "91") (name "unconnected-(HC-05-PIO0-Pad23)") (class "Default")
      (node (ref "HC-05") (pin "23") (pinfunction "PIO0_23") (pintype "bidirectional"))
    )
    (net (code "92") (name "unconnected-(HC-05-PIO1-Pad24)") (class "Default")
      (node (ref "HC-05") (pin "24") (pinfunction "PIO1_24") (pintype "bidirectional"))
    )
    (net (code "93") (name "unconnected-(HC-05-PIO2-Pad25)") (class "Default")
      (node (ref "HC-05") (pin "25") (pinfunction "PIO2_25") (pintype "bidirectional"))
    )
    (net (code "94") (name "unconnected-(HC-05-PIO3-Pad26)") (class "Default")
      (node (ref "HC-05") (pin "26") (pinfunction "PIO3_26") (pintype "bidirectional"))
    )
    (net (code "95") (name "unconnected-(HC-05-PIO4-Pad27)") (class "Default")
      (node (ref "HC-05") (pin "27") (pinfunction "PIO4_27") (pintype "bidirectional"))
    )
    (net (code "96") (name "unconnected-(HC-05-PIO5-Pad28)") (class "Default")
      (node (ref "HC-05") (pin "28") (pinfunction "PIO5_28") (pintype "bidirectional"))
    )
    (net (code "97") (name "unconnected-(HC-05-PIO6-Pad29)") (class "Default")
      (node (ref "HC-05") (pin "29") (pinfunction "PIO6_29") (pintype "bidirectional"))
    )
    (net (code "98") (name "unconnected-(HC-05-PIO7-Pad30)") (class "Default")
      (node (ref "HC-05") (pin "30") (pinfunction "PIO7_30") (pintype "bidirectional"))
    )
    (net (code "99") (name "unconnected-(HC-05-PIO10-Pad33)") (class "Default")
      (node (ref "HC-05") (pin "33") (pinfunction "PIO10_33") (pintype "bidirectional"))
    )
    (net (code "100") (name "unconnected-(HC-05-RST-Pad11)") (class "Default")
      (node (ref "HC-05") (pin "11") (pinfunction "RST_11") (pintype "bidirectional"))
    )
    (net (code "101") (name "unconnected-(HC-05-RTS-Pad4)") (class "Default")
      (node (ref "HC-05") (pin "4") (pinfunction "RTS_4") (pintype "bidirectional"))
    )
    (net (code "102") (name "unconnected-(HC-05-VBUSD+-Pad20)") (class "Default")
      (node (ref "HC-05") (pin "20") (pinfunction "VBUSD+_20") (pintype "bidirectional"))
    )
    (net (code "103") (name "unconnected-(HC-05-VBUSD--Pad15)") (class "Default")
      (node (ref "HC-05") (pin "15") (pinfunction "VBUSD-_15") (pintype "bidirectional"))
    )
    (net (code "104") (name "unconnected-(U$1-SQW-Pad7)") (class "Default")
      (node (ref "U$1") (pin "7") (pinfunction "SQW_7") (pintype "bidirectional"))
    )
    (net (code "105") (name "unconnected-(U1-N{slash}A-PadRESERVED)") (class "Default")
      (node (ref "U1") (pin "RESERVED") (pinfunction "N/A_RESERVED") (pintype "no_connect"))
    )
    (net (code "106") (name "unconnected-(U1-PadAREF)") (class "Default")
      (node (ref "U1") (pin "AREF") (pinfunction "AREF_AREF") (pintype "bidirectional"))
    )
    (net (code "107") (name "unconnected-(U1-PadIOREF)") (class "Default")
      (node (ref "U1") (pin "IOREF") (pinfunction "IOREF_IOREF") (pintype "output"))
    )
    (net (code "108") (name "unconnected-(U1-{slash}RESET-PadRESET)") (class "Default")
      (node (ref "U1") (pin "RESET") (pinfunction "/RESET_RESET") (pintype "bidirectional"))
    )
    (net (code "109") (name "unconnected-(U2-INT1-Pad11)") (class "Default")
      (node (ref "U2") (pin "11") (pinfunction "INT1_11") (pintype "bidirectional"))
    )
    (net (code "110") (name "unconnected-(U2-INT2-Pad9)") (class "Default")
      (node (ref "U2") (pin "9") (pinfunction "INT2_9") (pintype "bidirectional"))
    )
  )
)
